# design.net
KiCad netlist of a schematic drawn in Altium Designer
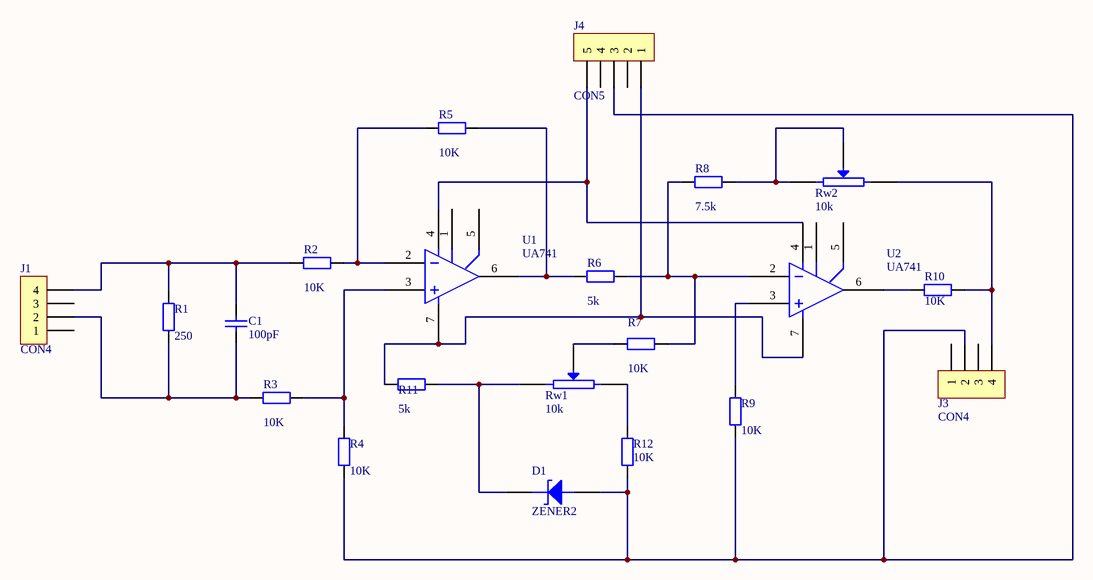
[diagram p0: 电流电压转换.SchDoc]

(export (version "E")
  (design (tool "Eeschema 10.0.6"))
  (components
    (comp (ref "C1")
      (value "100pF")
      (footprint "RAD-0.1")
      (description "Capacitor")
      (fields (field (name "Comment") "Cap") (field (name "PUBLISHER") "Altium Limited"))
      (libsource (lib "Miscellaneous Devices") (part "Cap"))
    )
    (comp (ref "D1")
      (value "ZENER2")
      (footprint "DIODE0.4")
      (description "Zener Diode")
      (libsource (lib "Miscellaneous Devices") (part "ZENER2"))
    )
    (comp (ref "J1")
      (value "CON4")
      (footprint "SIP4")
      (description "Connector")
      (libsource (lib "Miscellaneous Devices") (part "CON4"))
    )
    (comp (ref "J3")
      (value "CON4")
      (footprint "SIP4")
      (description "Connector")
      (libsource (lib "Miscellaneous Devices") (part "CON4"))
    )
    (comp (ref "J4")
      (value "CON5")
      (footprint "POWER PLUG5")
      (description "Connector")
      (libsource (lib "Miscellaneous Devices") (part "CON5"))
    )
    (comp (ref "R1")
      (value "250")
      (footprint "AXIAL-0.4")
      (description "Resistor")
      (fields (field (name "Comment") "Res2") (field (name "PUBLISHER") "Altium Limited"))
      (libsource (lib "") (part "Res2_1"))
    )
    (comp (ref "R2")
      (value "10K")
      (footprint "AXIAL-0.4")
      (description "Resistor")
      (fields (field (name "Comment") "Res2") (field (name "PUBLISHER") "Altium Limited"))
      (libsource (lib "Miscellaneous Devices") (part "Res2"))
    )
    (comp (ref "R3")
      (value "10K")
      (footprint "AXIAL-0.4")
      (description "Resistor")
      (fields (field (name "Comment") "Res2") (field (name "PUBLISHER") "Altium Limited"))
      (libsource (lib "Miscellaneous Devices") (part "Res2"))
    )
    (comp (ref "R4")
      (value "10K")
      (footprint "AXIAL-0.4")
      (description "Resistor")
      (fields (field (name "Comment") "Res2") (field (name "PUBLISHER") "Altium Limited"))
      (libsource (lib "") (part "Res2_1"))
    )
    (comp (ref "R5")
      (value "10K")
      (footprint "AXIAL-0.4")
      (description "Resistor")
      (fields (field (name "Comment") "Res2") (field (name "PUBLISHER") "Altium Limited"))
      (libsource (lib "Miscellaneous Devices") (part "Res2"))
    )
    (comp (ref "R6")
      (value "5k")
      (footprint "AXIAL-0.4")
      (description "Resistor")
      (fields (field (name "Comment") "Res2") (field (name "PUBLISHER") "Altium Limited"))
      (libsource (lib "Miscellaneous Devices") (part "Res2"))
    )
    (comp (ref "R7")
      (value "10K")
      (footprint "AXIAL-0.4")
      (description "Resistor")
      (fields (field (name "Comment") "Res2") (field (name "PUBLISHER") "Altium Limited"))
      (libsource (lib "Miscellaneous Devices") (part "Res2"))
    )
    (comp (ref "R8")
      (value "7.5k")
      (footprint "AXIAL-0.4")
      (description "Resistor")
      (fields (field (name "Comment") "Res2") (field (name "PUBLISHER") "Altium Limited"))
      (libsource (lib "Miscellaneous Devices") (part "Res2"))
    )
    (comp (ref "R9")
      (value "10K")
      (footprint "AXIAL-0.4")
      (description "Resistor")
      (fields (field (name "Comment") "Res2") (field (name "PUBLISHER") "Altium Limited"))
      (libsource (lib "") (part "Res2_1"))
    )
    (comp (ref "R10")
      (value "10K")
      (footprint "AXIAL-0.4")
      (description "Resistor")
      (fields (field (name "Comment") "Res2") (field (name "PUBLISHER") "Altium Limited"))
      (libsource (lib "") (part "Res2_3"))
    )
    (comp (ref "R11")
      (value "5k")
      (footprint "AXIAL-0.4")
      (description "Resistor")
      (fields (field (name "Comment") "Res2") (field (name "PUBLISHER") "Altium Limited"))
      (libsource (lib "Miscellaneous Devices") (part "Res2"))
    )
    (comp (ref "R12")
      (value "10K")
      (footprint "AXIAL-0.4")
      (description "Resistor")
      (fields (field (name "Comment") "Res2") (field (name "PUBLISHER") "Altium Limited"))
      (libsource (lib "") (part "Res2_2"))
    )
    (comp (ref "Rw1")
      (value "10k")
      (footprint "RP3296")
      (description "Potentiometer")
      (libsource (lib "Miscellaneous Devices") (part "POT2"))
    )
    (comp (ref "Rw2")
      (value "10k")
      (footprint "RP3296")
      (description "Potentiometer")
      (libsource (lib "Miscellaneous Devices") (part "POT2"))
    )
    (comp (ref "U1")
      (value "UA741")
      (footprint "DIP-8")
      (libsource (lib "Schematic Operational Amplifiers") (part "UA741"))
    )
    (comp (ref "U2")
      (value "UA741")
      (footprint "DIP-8")
      (libsource (lib "Schematic Operational Amplifiers") (part "UA741"))
    )
  )
  (nets
    (net (code "1") (name "Net-(C1-Pad1)") (class "Default")
      (node (ref "C1") (pin "1") (pinfunction "1_1") (pintype "passive"))
      (node (ref "J1") (pin "4") (pinfunction "4_4") (pintype "passive"))
      (node (ref "R1") (pin "2") (pinfunction "2_2") (pintype "passive"))
      (node (ref "R2") (pin "1") (pinfunction "1_1") (pintype "passive"))
    )
    (net (code "2") (name "Net-(C1-Pad2)") (class "Default")
      (node (ref "C1") (pin "2") (pinfunction "2_2") (pintype "passive"))
      (node (ref "J1") (pin "2") (pinfunction "2_2") (pintype "passive"))
      (node (ref "R1") (pin "1") (pinfunction "1_1") (pintype "passive"))
      (node (ref "R3") (pin "1") (pinfunction "1_1") (pintype "passive"))
    )
    (net (code "3") (name "Net-(D1-PadA)") (class "Default")
      (node (ref "D1") (pin "A") (pinfunction "A_A") (pintype "passive"))
      (node (ref "R11") (pin "2") (pinfunction "2_2") (pintype "passive"))
      (node (ref "Rw1") (pin "1") (pinfunction "1_1") (pintype "passive"))
    )
    (net (code "4") (name "Net-(D1-PadK)") (class "Default")
      (node (ref "D1") (pin "K") (pinfunction "K_K") (pintype "passive"))
      (node (ref "J3") (pin "2") (pinfunction "2_2") (pintype "passive"))
      (node (ref "J4") (pin "3") (pinfunction "3_3") (pintype "passive"))
      (node (ref "R12") (pin "2") (pinfunction "2_2") (pintype "passive"))
      (node (ref "R4") (pin "1") (pinfunction "1_1") (pintype "passive"))
      (node (ref "R9") (pin "1") (pinfunction "1_1") (pintype "passive"))
    )
    (net (code "5") (name "Net-(J3-Pad4)") (class "Default")
      (node (ref "J3") (pin "4") (pinfunction "4_4") (pintype "passive"))
      (node (ref "R10") (pin "1") (pinfunction "1_1") (pintype "passive"))
      (node (ref "Rw2") (pin "2") (pinfunction "2_2") (pintype "passive"))
    )
    (net (code "6") (name "Net-(J4-Pad1)") (class "Default")
      (node (ref "J4") (pin "1") (pinfunction "1_1") (pintype "passive"))
      (node (ref "R11") (pin "1") (pinfunction "1_1") (pintype "passive"))
      (node (ref "U1") (pin "7") (pintype "passive"))
      (node (ref "U2") (pin "7") (pintype "passive"))
    )
    (net (code "7") (name "Net-(J4-Pad5)") (class "Default")
      (node (ref "J4") (pin "5") (pinfunction "5_5") (pintype "passive"))
      (node (ref "U1") (pin "4") (pintype "passive"))
      (node (ref "U2") (pin "4") (pintype "passive"))
    )
    (net (code "8") (name "Net-(R2-Pad2)") (class "Default")
      (node (ref "R2") (pin "2") (pinfunction "2_2") (pintype "passive"))
      (node (ref "R5") (pin "1") (pinfunction "1_1") (pintype "passive"))
      (node (ref "U1") (pin "2") (pintype "passive"))
    )
    (net (code "9") (name "Net-(R3-Pad2)") (class "Default")
      (node (ref "R3") (pin "2") (pinfunction "2_2") (pintype "passive"))
      (node (ref "R4") (pin "2") (pinfunction "2_2") (pintype "passive"))
      (node (ref "U1") (pin "3") (pintype "passive"))
    )
    (net (code "10") (name "Net-(R5-Pad2)") (class "Default")
      (node (ref "R5") (pin "2") (pinfunction "2_2") (pintype "passive"))
      (node (ref "R6") (pin "1") (pinfunction "1_1") (pintype "passive"))
      (node (ref "U1") (pin "6") (pintype "passive"))
    )
    (net (code "11") (name "Net-(R6-Pad2)") (class "Default")
      (node (ref "R6") (pin "2") (pinfunction "2_2") (pintype "passive"))
      (node (ref "R7") (pin "2") (pinfunction "2_2") (pintype "passive"))
      (node (ref "R8") (pin "1") (pinfunction "1_1") (pintype "passive"))
      (node (ref "U2") (pin "2") (pintype "passive"))
    )
    (net (code "12") (name "Net-(R9-Pad2)") (class "Default")
      (node (ref "R9") (pin "2") (pinfunction "2_2") (pintype "passive"))
      (node (ref "U2") (pin "3") (pintype "passive"))
    )
    (net (code "13") (name "Net-(R10-Pad2)") (class "Default")
      (node (ref "R10") (pin "2") (pinfunction "2_2") (pintype "passive"))
      (node (ref "U2") (pin "6") (pintype "passive"))
    )
    (net (code "14") (name "Net-(R12-Pad1)") (class "Default")
      (node (ref "R12") (pin "1") (pinfunction "1_1") (pintype "passive"))
      (node (ref "Rw1") (pin "2") (pinfunction "2_2") (pintype "passive"))
    )
    (net (code "15") (name "Net-(Rw1-W)") (class "Default")
      (node (ref "R7") (pin "1") (pinfunction "1_1") (pintype "passive"))
      (node (ref "Rw1") (pin "3") (pinfunction "W_3") (pintype "passive"))
    )
    (net (code "16") (name "Net-(Rw2-W)") (class "Default")
      (node (ref "R8") (pin "2") (pinfunction "2_2") (pintype "passive"))
      (node (ref "Rw2") (pin "1") (pinfunction "1_1") (pintype "passive"))
      (node (ref "Rw2") (pin "3") (pinfunction "W_3") (pintype "passive"))
    )
    (net (code "17") (name "unconnected-(J1-Pad1)") (class "Default")
      (node (ref "J1") (pin "1") (pinfunction "1_1") (pintype "passive"))
    )
    (net (code "18") (name "unconnected-(J1-Pad3)") (class "Default")
      (node (ref "J1") (pin "3") (pinfunction "3_3") (pintype "passive"))
    )
    (net (code "19") (name "unconnected-(J3-Pad1)") (class "Default")
      (node (ref "J3") (pin "1") (pinfunction "1_1") (pintype "passive"))
    )
    (net (code "20") (name "unconnected-(J3-Pad3)") (class "Default")
      (node (ref "J3") (pin "3") (pinfunction "3_3") (pintype "passive"))
    )
    (net (code "21") (name "unconnected-(J4-Pad2)") (class "Default")
      (node (ref "J4") (pin "2") (pinfunction "2_2") (pintype "passive"))
    )
    (net (code "22") (name "unconnected-(J4-Pad4)") (class "Default")
      (node (ref "J4") (pin "4") (pinfunction "4_4") (pintype "passive"))
    )
    (net (code "23") (name "unconnected-(U1-Pad1)") (class "Default")
      (node (ref "U1") (pin "1") (pintype "passive"))
    )
    (net (code "24") (name "unconnected-(U1-Pad5)") (class "Default")
      (node (ref "U1") (pin "5") (pintype "passive"))
    )
    (net (code "25") (name "unconnected-(U2-Pad1)") (class "Default")
      (node (ref "U2") (pin "1") (pintype "passive"))
    )
    (net (code "26") (name "unconnected-(U2-Pad5)") (class "Default")
      (node (ref "U2") (pin "5") (pintype "passive"))
    )
  )
)
